# 5vto3_3v.net
KiCad netlist of a schematic drawn in Altium Designer
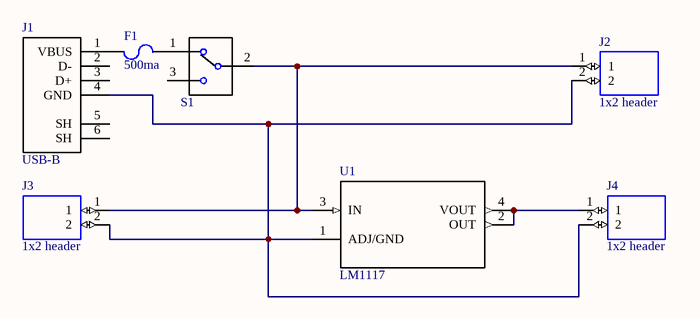
[diagram p0: 5vto3.3v.SchDoc]

(export (version "E")
  (design (tool "Eeschema 10.0.6"))
  (components
    (comp (ref "F1")
      (value "500ma")
      (footprint "Fuse 0603")
      (description "FUSE BOARD MOUNT 500MA 32VAC/VDC")
      (fields
        (field (name "MANUFACTURER") "Littelfuse")
        (field (name "MANUFACTURER PART NUMBER") "0494.500NRHF")
      )
      (libsource (lib "5vto3.3v") (part "0494.500NRHF"))
    )
    (comp (ref "J1")
      (value "USB-B")
      (footprint "SAMTEC_USB-B-S-S-B-VT-R")
      (description "MOLEX         67068-8000            USB, 2.0 TYPE B, RECEPTACLE, THT")
      (fields (field (name "MANUFACTURER") "Molex") (field (name "MANUFACTURER PART NUMBER") "67068-8000"))
      (libsource (lib "5vto3.3v") (part "67068-8000"))
    )
    (comp (ref "J2")
      (value "1x2 header")
      (footprint "B2B-XH-A(LF)(SN)")
      (description "HEADER, VERTICAL, 2WAY")
      (fields
        (field (name "MANUFACTURER") "JST")
        (field (name "MANUFACTURER PART NUMBER") "B2B-XH-A(LF)(SN)")
      )
      (libsource (lib "5vto3.3v") (part "B2B-XH-A(LF)(SN)"))
    )
    (comp (ref "J3")
      (value "1x2 header")
      (footprint "B2B-XH-A(LF)(SN)")
      (description "HEADER, VERTICAL, 2WAY")
      (fields
        (field (name "MANUFACTURER") "JST")
        (field (name "MANUFACTURER PART NUMBER") "B2B-XH-A(LF)(SN)")
      )
      (libsource (lib "5vto3.3v") (part "B2B-XH-A(LF)(SN)"))
    )
    (comp (ref "J4")
      (value "1x2 header")
      (footprint "B2B-XH-A(LF)(SN)")
      (description "HEADER, VERTICAL, 2WAY")
      (fields
        (field (name "MANUFACTURER") "JST")
        (field (name "MANUFACTURER PART NUMBER") "B2B-XH-A(LF)(SN)")
      )
      (libsource (lib "5vto3.3v") (part "B2B-XH-A(LF)(SN)"))
    )
    (comp (ref "S1")
      (value "TOGGLE SWITCH")
      (footprint "A101SYCQ04")
      (description "Toggle Switches ON-ON SPDT Bat Long")
      (fields
        (field (name "MANUFACTURER") "TE Connectivity")
        (field (name "MANUFACTURER PART NUMBER") "A101SYCQ04")
      )
      (libsource (lib "5vto3.3v") (part "A101SYCQ04"))
    )
    (comp (ref "U1")
      (value "LM1117")
      (footprint "LM1117MP-3.3")
      (description "TEXAS INSTRUMENTS   LM1117MPX-3.3/NOPB.   LINEAR REG, FIX, 3.3V, 800MA, SOT-223-4, FULL REEL")
      (fields
        (field (name "MANUFACTURER") "Texas Instruments")
        (field (name "MANUFACTURER PART NUMBER") "LM1117MPX-3.3/NOPB")
      )
      (libsource (lib "5vto3.3v") (part "LM1117MPX-3.3/NOPB"))
    )
  )
  (nets
    (net (code "1") (name "Net-(F1-Pad1)") (class "Default")
      (node (ref "F1") (pin "1") (pinfunction "1_1") (pintype "passive"))
      (node (ref "S1") (pin "1") (pinfunction "1_1") (pintype "passive"))
    )
    (net (code "2") (name "Net-(J1-GND)") (class "Default")
      (node (ref "J1") (pin "4") (pinfunction "GND_4") (pintype "passive"))
      (node (ref "J2") (pin "2") (pinfunction "2_2") (pintype "bidirectional"))
      (node (ref "J3") (pin "2") (pinfunction "2_2") (pintype "bidirectional"))
      (node (ref "J4") (pin "2") (pinfunction "2_2") (pintype "bidirectional"))
      (node (ref "U1") (pin "1") (pinfunction "ADJ/GND_1") (pintype "passive"))
    )
    (net (code "3") (name "Net-(U1-IN)") (class "Default")
      (node (ref "J2") (pin "1") (pinfunction "1_1") (pintype "bidirectional"))
      (node (ref "J3") (pin "1") (pinfunction "1_1") (pintype "bidirectional"))
      (node (ref "S1") (pin "2") (pinfunction "2_2") (pintype "passive"))
      (node (ref "U1") (pin "3") (pinfunction "IN_3") (pintype "input"))
    )
    (net (code "4") (name "Net-(U1-OUT)") (class "Default")
      (node (ref "J4") (pin "1") (pinfunction "1_1") (pintype "bidirectional"))
      (node (ref "U1") (pin "2") (pinfunction "OUT_2") (pintype "output"))
      (node (ref "U1") (pin "4") (pinfunction "VOUT_4") (pintype "output"))
    )
    (net (code "5") (name "unconnected-(F1-Pad2)") (class "Default")
      (node (ref "F1") (pin "2") (pinfunction "2_2") (pintype "passive"))
    )
    (net (code "6") (name "unconnected-(J1-D+-Pad3)") (class "Default")
      (node (ref "J1") (pin "3") (pinfunction "D+_3") (pintype "passive"))
    )
    (net (code "7") (name "unconnected-(J1-D--Pad2)") (class "Default")
      (node (ref "J1") (pin "2") (pinfunction "D-_2") (pintype "passive"))
    )
    (net (code "8") (name "unconnected-(J1-SH-Pad5)") (class "Default")
      (node (ref "J1") (pin "5") (pinfunction "SH_5") (pintype "passive"))
    )
    (net (code "9") (name "unconnected-(J1-SH-Pad6)") (class "Default")
      (node (ref "J1") (pin "6") (pinfunction "SH_6") (pintype "passive"))
    )
    (net (code "10") (name "unconnected-(J1-VBUS-Pad1)") (class "Default")
      (node (ref "J1") (pin "1") (pinfunction "VBUS_1") (pintype "passive"))
    )
    (net (code "11") (name "unconnected-(S1-Pad3)") (class "Default")
      (node (ref "S1") (pin "3") (pinfunction "3_3") (pintype "passive"))
    )
  )
)
